# Sheet1.net
KiCad netlist of a schematic drawn in Altium Designer
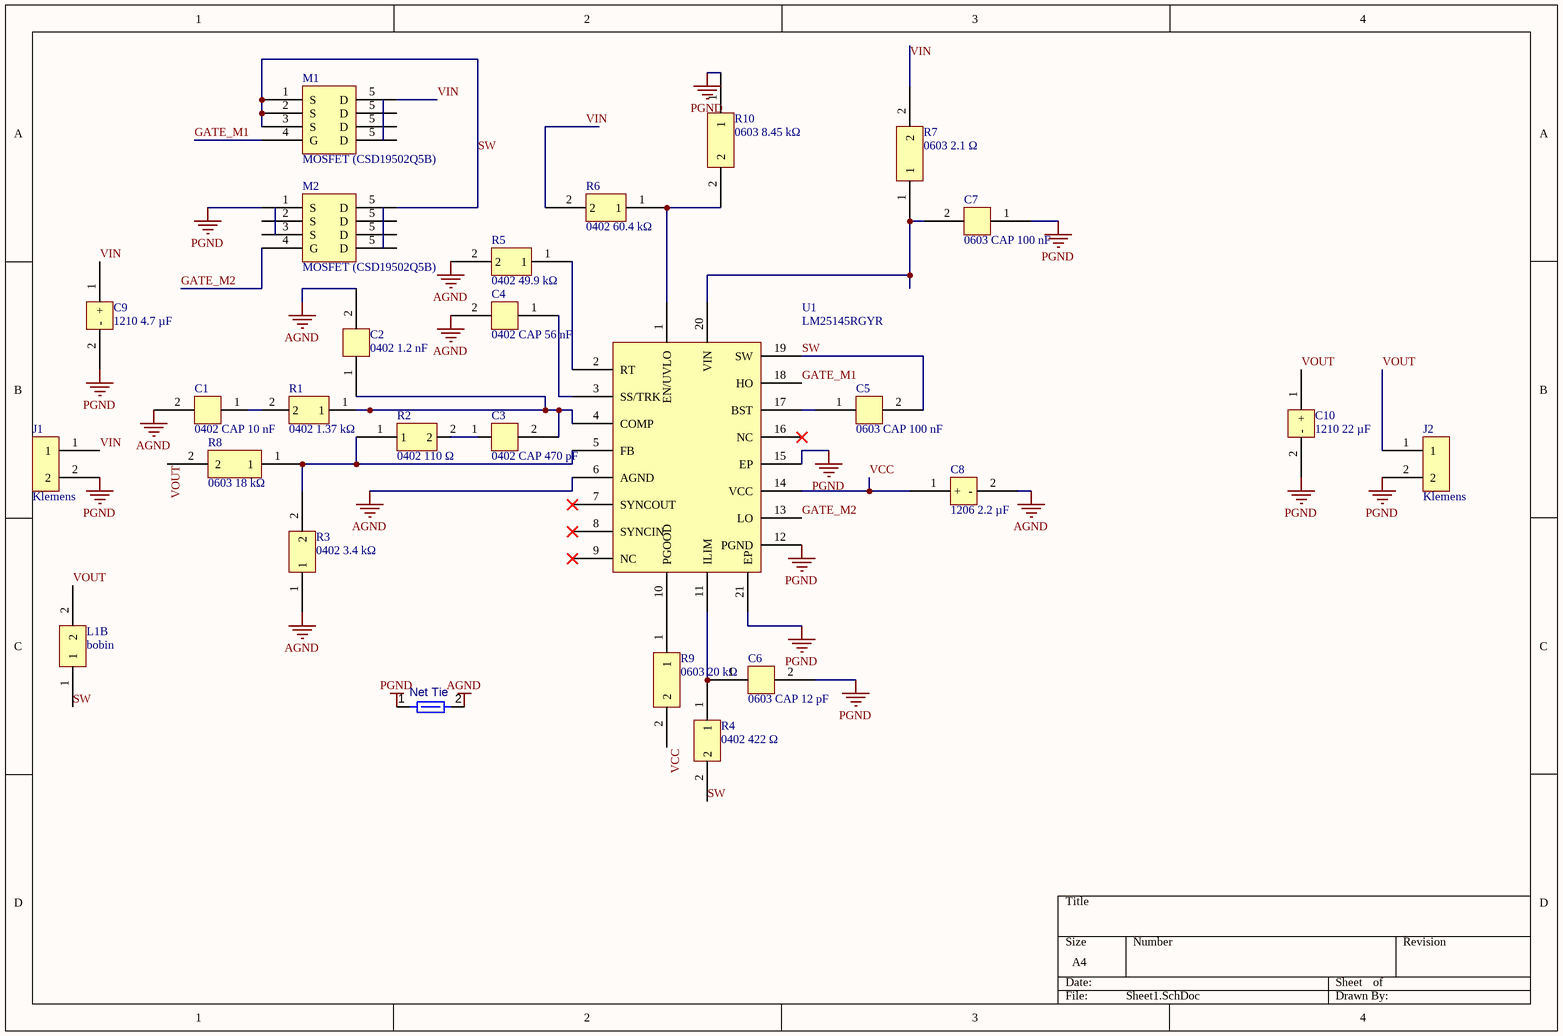
[diagram p0: Sheet1.SchDoc]

(export (version "E")
  (design (tool "Eeschema 10.0.6"))
  (components
    (comp (ref "C1")
      (value "0402 CAP 10 nF")
      (footprint "RESC1005X06N")
      (libsource (lib "Schlib2") (part "0402 CAP"))
    )
    (comp (ref "C2")
      (value "0402 1.2 nF")
      (footprint "RESC1005X06N")
      (libsource (lib "") (part "0402 CAP_1"))
    )
    (comp (ref "C3")
      (value "0402 CAP 470 pF")
      (footprint "RESC1005X06N")
      (libsource (lib "") (part "0402 CAP_2"))
    )
    (comp (ref "C4")
      (value "0402 CAP 56 nF")
      (footprint "RESC1005X06N")
      (libsource (lib "Schlib2") (part "0402 CAP"))
    )
    (comp (ref "C5")
      (value "0603 CAP 100 nF")
      (footprint "RESC1608X06N")
      (libsource (lib "Schlib2") (part "0603 CAP"))
    )
    (comp (ref "C6")
      (value "0603 CAP 12 pF")
      (footprint "RESC1608X06N")
      (libsource (lib "Schlib2") (part "0603 CAP"))
    )
    (comp (ref "C7")
      (value "0603 CAP 100 nF")
      (footprint "RESC1608X06N")
      (libsource (lib "") (part "0603 CAP_1"))
    )
    (comp (ref "C8")
      (value "1206 2.2 µF")
      (footprint "1206 (Orta Boy Seramik)")
      (libsource (lib "Schlib2") (part "1206 orta boy kondansatör"))
    )
    (comp (ref "C9")
      (value "1210 4.7 µF")
      (footprint "1210 (En Büyük Seramik)")
      (libsource (lib "Schlib2") (part "1210 kondansatör"))
    )
    (comp (ref "C10")
      (value "1210 22 µF")
      (footprint "1210 (En Büyük Seramik)")
      (libsource (lib "Schlib2") (part "1210 kondansatör"))
    )
    (comp (ref "J1") (value "Klemens") (footprint "Klemens") (libsource (lib "Schlib2") (part "Klemens")))
    (comp (ref "J2") (value "Klemens") (footprint "Klemens") (libsource (lib "") (part "Klemens_1")))
    (comp (ref "L1") (value "bobin") (footprint "INDM150150X100N") (libsource (lib "Schlib2") (part "bobin")))
    (comp (ref "M1")
      (value "MOSFET (CSD19502Q5B)")
      (footprint "MOSFET+")
      (libsource (lib "Schlib2") (part "MOSFET (CSD19502Q5B)"))
    )
    (comp (ref "M2")
      (value "MOSFET (CSD19502Q5B)")
      (footprint "MOSFET+")
      (libsource (lib "Schlib2") (part "MOSFET (CSD19502Q5B)"))
    )
    (comp (ref "Net Tie")
      (value "Net Tie 10x8mil")
      (footprint "New footprint 1")
      (libsource (lib "zorlusuleyman394") (part "CMP-00022-00002-2"))
    )
    (comp (ref "R1")
      (value "0402 1.37 kΩ")
      (footprint "RESC1608X06N")
      (libsource (lib "Schlib2") (part "direnç 0402"))
    )
    (comp (ref "R2")
      (value "0402 110 Ω")
      (footprint "RESC1608X06N")
      (libsource (lib "") (part "direnç 0402_3"))
    )
    (comp (ref "R3")
      (value "0402 3.4 kΩ")
      (footprint "RESC1608X06N")
      (libsource (lib "") (part "direnç 0402_2"))
    )
    (comp (ref "R4")
      (value "0402 422 Ω")
      (footprint "RESC1608X06N")
      (libsource (lib "") (part "direnç 0402_1"))
    )
    (comp (ref "R5")
      (value "0402 49.9 kΩ")
      (footprint "RESC1608X06N")
      (libsource (lib "Schlib2") (part "direnç 0402"))
    )
    (comp (ref "R6")
      (value "0402 60.4 kΩ")
      (footprint "RESC1608X06N")
      (libsource (lib "Schlib2") (part "direnç 0402"))
    )
    (comp (ref "R7") (value "0603 2.1 Ω") (footprint "RESC1608X06N") (libsource (lib "") (part "direnç_2")))
    (comp (ref "R8")
      (value "0603 18 kΩ")
      (footprint "RESC1608X06N")
      (libsource (lib "Schlib2") (part "direnç"))
    )
    (comp (ref "R9") (value "0603 20 kΩ") (footprint "RESC1608X06N") (libsource (lib "") (part "direnç_1")))
    (comp (ref "R10")
      (value "0603 8.45 kΩ")
      (footprint "RESC1608X06N")
      (libsource (lib "") (part "direnç_1"))
    )
    (comp (ref "U1")
      (value "LM25145RGYR")
      (footprint "PQFN50P350X450X100_HS-21N")
      (libsource (lib "Schlib2") (part "LM25145RGYR"))
    )
  )
  (nets
    (net (code "1") (name "/GATE_M1") (class "Default")
      (node (ref "M1") (pin "4") (pinfunction "G_4") (pintype "passive"))
      (node (ref "U1") (pin "18") (pinfunction "HO_18") (pintype "passive"))
    )
    (net (code "2") (name "/GATE_M2") (class "Default")
      (node (ref "M2") (pin "4") (pinfunction "G_4") (pintype "passive"))
      (node (ref "U1") (pin "13") (pinfunction "LO_13") (pintype "passive"))
    )
    (net (code "3") (name "/SW") (class "Default")
      (node (ref "C5") (pin "2") (pintype "passive"))
      (node (ref "L1") (pin "1") (pinfunction "1_1") (pintype "passive"))
      (node (ref "M1") (pin "1") (pinfunction "S_1") (pintype "passive"))
      (node (ref "M1") (pin "2") (pinfunction "S_2") (pintype "passive"))
      (node (ref "M1") (pin "3") (pinfunction "S_3") (pintype "passive"))
      (node (ref "M2") (pin "5") (pinfunction "D_5") (pintype "passive"))
      (node (ref "R4") (pin "2") (pinfunction "2_2") (pintype "passive"))
      (node (ref "U1") (pin "19") (pinfunction "SW_19") (pintype "passive"))
    )
    (net (code "4") (name "/VCC") (class "Default")
      (node (ref "C8") (pin "1") (pinfunction "+_1") (pintype "passive"))
      (node (ref "R9") (pin "2") (pinfunction "2_2") (pintype "passive"))
      (node (ref "U1") (pin "14") (pinfunction "VCC_14") (pintype "passive"))
    )
    (net (code "5") (name "/VIN") (class "Default")
      (node (ref "C9") (pin "1") (pinfunction "+_1") (pintype "passive"))
      (node (ref "J1") (pin "1") (pinfunction "1_1") (pintype "passive"))
      (node (ref "M1") (pin "5") (pinfunction "D_5") (pintype "passive"))
      (node (ref "R6") (pin "2") (pinfunction "2_2") (pintype "passive"))
      (node (ref "R7") (pin "2") (pinfunction "2_2") (pintype "passive"))
    )
    (net (code "6") (name "/VOUT") (class "Default")
      (node (ref "C10") (pin "1") (pinfunction "+_1") (pintype "passive"))
      (node (ref "J2") (pin "1") (pinfunction "1_1") (pintype "passive"))
      (node (ref "L1") (pin "2") (pinfunction "2_2") (pintype "passive"))
      (node (ref "R8") (pin "2") (pinfunction "2_2") (pintype "passive"))
    )
    (net (code "7") (name "AGND") (class "Default")
      (node (ref "C1") (pin "2") (pintype "passive"))
      (node (ref "C2") (pin "2") (pintype "passive"))
      (node (ref "C4") (pin "2") (pintype "passive"))
      (node (ref "C8") (pin "2") (pinfunction "-_2") (pintype "passive"))
      (node (ref "Net Tie") (pin "2") (pinfunction "2_2") (pintype "passive"))
      (node (ref "R3") (pin "1") (pinfunction "1_1") (pintype "passive"))
      (node (ref "R5") (pin "2") (pinfunction "2_2") (pintype "passive"))
      (node (ref "U1") (pin "6") (pinfunction "AGND_6") (pintype "passive"))
    )
    (net (code "8") (name "Net-(C1-Pad1)") (class "Default")
      (node (ref "C1") (pin "1") (pintype "passive"))
      (node (ref "R1") (pin "2") (pinfunction "2_2") (pintype "passive"))
    )
    (net (code "9") (name "Net-(C3-Pad1)") (class "Default")
      (node (ref "C3") (pin "1") (pintype "passive"))
      (node (ref "R2") (pin "2") (pinfunction "2_2") (pintype "passive"))
    )
    (net (code "10") (name "Net-(U1-BST)") (class "Default")
      (node (ref "C5") (pin "1") (pintype "passive"))
      (node (ref "U1") (pin "17") (pinfunction "BST_17") (pintype "passive"))
    )
    (net (code "11") (name "Net-(U1-COMP)") (class "Default")
      (node (ref "C2") (pin "1") (pintype "passive"))
      (node (ref "C3") (pin "2") (pintype "passive"))
      (node (ref "R1") (pin "1") (pinfunction "1_1") (pintype "passive"))
      (node (ref "U1") (pin "4") (pinfunction "COMP_4") (pintype "passive"))
    )
    (net (code "12") (name "Net-(U1-EN{slash}UVLO)") (class "Default")
      (node (ref "R10") (pin "2") (pinfunction "2_2") (pintype "passive"))
      (node (ref "R6") (pin "1") (pinfunction "1_1") (pintype "passive"))
      (node (ref "U1") (pin "1") (pinfunction "EN/UVLO_1") (pintype "passive"))
    )
    (net (code "13") (name "Net-(U1-FB)") (class "Default")
      (node (ref "R2") (pin "1") (pinfunction "1_1") (pintype "passive"))
      (node (ref "R3") (pin "2") (pinfunction "2_2") (pintype "passive"))
      (node (ref "R8") (pin "1") (pinfunction "1_1") (pintype "passive"))
      (node (ref "U1") (pin "5") (pinfunction "FB_5") (pintype "passive"))
    )
    (net (code "14") (name "Net-(U1-ILIM)") (class "Default")
      (node (ref "C6") (pin "1") (pintype "passive"))
      (node (ref "R4") (pin "1") (pinfunction "1_1") (pintype "passive"))
      (node (ref "U1") (pin "11") (pinfunction "ILIM_11") (pintype "passive"))
    )
    (net (code "15") (name "Net-(U1-PGOOD)") (class "Default")
      (node (ref "R9") (pin "1") (pinfunction "1_1") (pintype "passive"))
      (node (ref "U1") (pin "10") (pinfunction "PGOOD_10") (pintype "passive"))
    )
    (net (code "16") (name "Net-(U1-RT)") (class "Default")
      (node (ref "R5") (pin "1") (pinfunction "1_1") (pintype "passive"))
      (node (ref "U1") (pin "2") (pinfunction "RT_2") (pintype "passive"))
    )
    (net (code "17") (name "Net-(U1-SS{slash}TRK)") (class "Default")
      (node (ref "C4") (pin "1") (pintype "passive"))
      (node (ref "U1") (pin "3") (pinfunction "SS/TRK_3") (pintype "passive"))
    )
    (net (code "18") (name "Net-(U1-VIN)") (class "Default")
      (node (ref "C7") (pin "2") (pintype "passive"))
      (node (ref "R7") (pin "1") (pinfunction "1_1") (pintype "passive"))
      (node (ref "U1") (pin "20") (pinfunction "VIN_20") (pintype "passive"))
    )
    (net (code "19") (name "PGND") (class "Default")
      (node (ref "C10") (pin "2") (pinfunction "-_2") (pintype "passive"))
      (node (ref "C6") (pin "2") (pintype "passive"))
      (node (ref "C7") (pin "1") (pintype "passive"))
      (node (ref "C9") (pin "2") (pinfunction "-_2") (pintype "passive"))
      (node (ref "J1") (pin "2") (pinfunction "2_2") (pintype "passive"))
      (node (ref "J2") (pin "2") (pinfunction "2_2") (pintype "passive"))
      (node (ref "M2") (pin "1") (pinfunction "S_1") (pintype "passive"))
      (node (ref "Net Tie") (pin "1") (pinfunction "1_1") (pintype "passive"))
      (node (ref "R10") (pin "1") (pinfunction "1_1") (pintype "passive"))
      (node (ref "U1") (pin "12") (pinfunction "PGND_12") (pintype "passive"))
      (node (ref "U1") (pin "15") (pinfunction "EP_15") (pintype "passive"))
      (node (ref "U1") (pin "21") (pinfunction "EP_21") (pintype "passive"))
    )
    (net (code "20") (name "unconnected-(M1-D-Pad5)") (class "Default")
      (node (ref "M1") (pin "5") (pinfunction "D_5") (pintype "passive"))
    )
    (net (code "21") (name "unconnected-(M1-D-Pad5)_1") (class "Default")
      (node (ref "M1") (pin "5") (pinfunction "D_5") (pintype "passive"))
    )
    (net (code "22") (name "unconnected-(M1-D-Pad5)_2") (class "Default")
      (node (ref "M1") (pin "5") (pinfunction "D_5") (pintype "passive"))
    )
    (net (code "23") (name "unconnected-(M2-D-Pad5)") (class "Default")
      (node (ref "M2") (pin "5") (pinfunction "D_5") (pintype "passive"))
    )
    (net (code "24") (name "unconnected-(M2-D-Pad5)_1") (class "Default")
      (node (ref "M2") (pin "5") (pinfunction "D_5") (pintype "passive"))
    )
    (net (code "25") (name "unconnected-(M2-D-Pad5)_2") (class "Default")
      (node (ref "M2") (pin "5") (pinfunction "D_5") (pintype "passive"))
    )
    (net (code "26") (name "unconnected-(M2-S-Pad2)") (class "Default")
      (node (ref "M2") (pin "2") (pinfunction "S_2") (pintype "passive"))
    )
    (net (code "27") (name "unconnected-(M2-S-Pad3)") (class "Default")
      (node (ref "M2") (pin "3") (pinfunction "S_3") (pintype "passive"))
    )
    (net (code "28") (name "unconnected-(U1-NC-Pad9)") (class "Default")
      (node (ref "U1") (pin "9") (pinfunction "NC_9") (pintype "passive+no_connect"))
    )
    (net (code "29") (name "unconnected-(U1-NC-Pad16)") (class "Default")
      (node (ref "U1") (pin "16") (pinfunction "NC_16") (pintype "passive+no_connect"))
    )
    (net (code "30") (name "unconnected-(U1-SYNCIN-Pad8)") (class "Default")
      (node (ref "U1") (pin "8") (pinfunction "SYNCIN_8") (pintype "passive+no_connect"))
    )
    (net (code "31") (name "unconnected-(U1-SYNCOUT-Pad7)") (class "Default")
      (node (ref "U1") (pin "7") (pinfunction "SYNCOUT_7") (pintype "passive+no_connect"))
    )
  )
)
